# Power_Conversion.net
KiCad netlist of a schematic drawn in Altium Designer
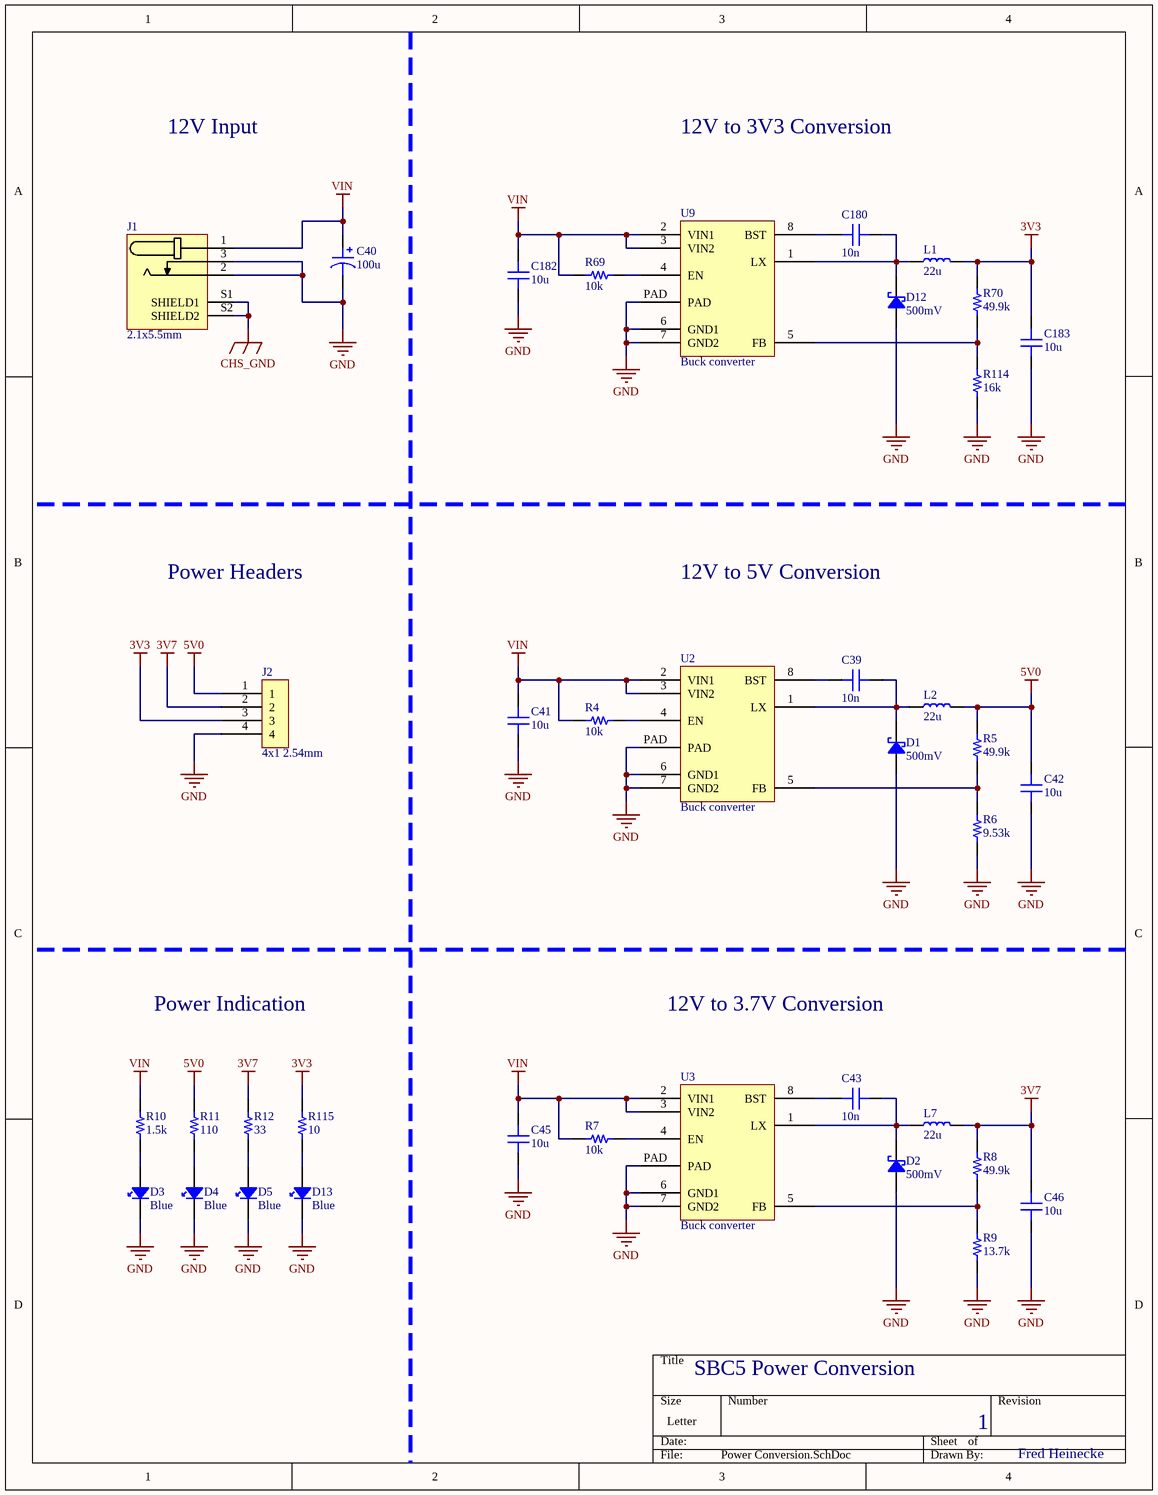
[diagram p0: Power Conversion.SchDoc]

(export (version "E")
  (design (tool "Eeschema 10.0.6"))
  (components
    (comp (ref "C39")
      (value "10n")
      (footprint "C0402")
      (fields
        (field (name "MANUFACTURER") "Samsung")
        (field (name "MANUFACTURER PART NUMBER") "CL05B103KO5NNNC")
        (field (name "TOLERANCE") "10%")
      )
      (libsource (lib "SBC5") (part "CL05B103KO5NNNC"))
    )
    (comp (ref "C40")
      (value "100u")
      (footprint "C8x11.5x3.5")
      (description "PANASONIC ELECTRONIC COMPONENTS - EEUFM1H101 - CAP, ALU ELEC, 100UF, 50V, RAD")
      (fields
        (field (name "MANUFACTURER") "Panasonic")
        (field (name "MANUFACTURER PART NUMBER") "EEU-FM1H101")
      )
      (libsource (lib "SBC5") (part "EEU-FM1H101"))
    )
    (comp (ref "C41")
      (value "10u")
      (footprint "C0805")
      (fields
        (field (name "MANUFACTURER") "Samsung")
        (field (name "MANUFACTURER PART NUMBER") "CL21A106KOQNNNE")
        (field (name "TOLERANCE") "10%")
      )
      (libsource (lib "SBC5") (part "CL21A106KOQNNNE"))
    )
    (comp (ref "C42")
      (value "10u")
      (footprint "C0805")
      (fields
        (field (name "MANUFACTURER") "Samsung")
        (field (name "MANUFACTURER PART NUMBER") "CL21A106KOQNNNE")
        (field (name "TOLERANCE") "10%")
      )
      (libsource (lib "SBC5") (part "CL21A106KOQNNNE"))
    )
    (comp (ref "C43")
      (value "10n")
      (footprint "C0402")
      (fields
        (field (name "MANUFACTURER") "Samsung")
        (field (name "MANUFACTURER PART NUMBER") "CL05B103KO5NNNC")
        (field (name "TOLERANCE") "10%")
      )
      (libsource (lib "SBC5") (part "CL05B103KO5NNNC"))
    )
    (comp (ref "C45")
      (value "10u")
      (footprint "C0805")
      (fields
        (field (name "MANUFACTURER") "Samsung")
        (field (name "MANUFACTURER PART NUMBER") "CL21A106KOQNNNE")
        (field (name "TOLERANCE") "10%")
      )
      (libsource (lib "SBC5") (part "CL21A106KOQNNNE"))
    )
    (comp (ref "C46")
      (value "10u")
      (footprint "C0805")
      (fields
        (field (name "MANUFACTURER") "Samsung")
        (field (name "MANUFACTURER PART NUMBER") "CL21A106KOQNNNE")
        (field (name "TOLERANCE") "10%")
      )
      (libsource (lib "SBC5") (part "CL21A106KOQNNNE"))
    )
    (comp (ref "C180")
      (value "10n")
      (footprint "C0402")
      (fields
        (field (name "MANUFACTURER") "Samsung")
        (field (name "MANUFACTURER PART NUMBER") "CL05B103KO5NNNC")
        (field (name "TOLERANCE") "10%")
      )
      (libsource (lib "SBC5") (part "CL05B103KO5NNNC"))
    )
    (comp (ref "C182")
      (value "10u")
      (footprint "C0805")
      (fields
        (field (name "MANUFACTURER") "Samsung")
        (field (name "MANUFACTURER PART NUMBER") "CL21A106KOQNNNE")
        (field (name "TOLERANCE") "10%")
      )
      (libsource (lib "SBC5") (part "CL21A106KOQNNNE"))
    )
    (comp (ref "C183")
      (value "10u")
      (footprint "C0805")
      (fields
        (field (name "MANUFACTURER") "Samsung")
        (field (name "MANUFACTURER PART NUMBER") "CL21A106KOQNNNE")
        (field (name "TOLERANCE") "10%")
      )
      (libsource (lib "SBC5") (part "CL21A106KOQNNNE"))
    )
    (comp (ref "D1")
      (value "500mV")
      (footprint "SOD-123")
      (description "Diode Schottky 30V 2A SOD123")
      (fields (field (name "MANUFACTURER") "SMC") (field (name "MANUFACTURER PART NUMBER") "MBR230LSTR"))
      (libsource (lib "SBC5") (part "MBR230LSTR"))
    )
    (comp (ref "D2")
      (value "500mV")
      (footprint "SOD-123")
      (description "Diode Schottky 30V 2A SOD123")
      (fields (field (name "MANUFACTURER") "SMC") (field (name "MANUFACTURER PART NUMBER") "MBR230LSTR"))
      (libsource (lib "SBC5") (part "MBR230LSTR"))
    )
    (comp (ref "D3")
      (value "Blue")
      (footprint "D0603")
      (description "WURTH ELEKTRONIK - 150060BS75000 - LED, Blau, Oberflächenmontage, 603, 30 mA, 3.2 V, 470 nm")
      (fields
        (field (name "MANUFACTURER") "Wurth Electronics")
        (field (name "MANUFACTURER PART NUMBER") "150060BS75000")
      )
      (libsource (lib "SBC5") (part "150060BS75000"))
    )
    (comp (ref "D4")
      (value "Blue")
      (footprint "D0603")
      (description "WURTH ELEKTRONIK - 150060BS75000 - LED, Blau, Oberflächenmontage, 603, 30 mA, 3.2 V, 470 nm")
      (fields
        (field (name "MANUFACTURER") "Wurth Electronics")
        (field (name "MANUFACTURER PART NUMBER") "150060BS75000")
      )
      (libsource (lib "SBC5") (part "150060BS75000"))
    )
    (comp (ref "D5")
      (value "Blue")
      (footprint "D0603")
      (description "WURTH ELEKTRONIK - 150060BS75000 - LED, Blau, Oberflächenmontage, 603, 30 mA, 3.2 V, 470 nm")
      (fields
        (field (name "MANUFACTURER") "Wurth Electronics")
        (field (name "MANUFACTURER PART NUMBER") "150060BS75000")
      )
      (libsource (lib "SBC5") (part "150060BS75000"))
    )
    (comp (ref "D12")
      (value "500mV")
      (footprint "SOD-123")
      (description "Diode Schottky 30V 2A SOD123")
      (fields (field (name "MANUFACTURER") "SMC") (field (name "MANUFACTURER PART NUMBER") "MBR230LSTR"))
      (libsource (lib "SBC5") (part "MBR230LSTR"))
    )
    (comp (ref "D13")
      (value "Blue")
      (footprint "D0603")
      (description "WURTH ELEKTRONIK - 150060BS75000 - LED, Blau, Oberflächenmontage, 603, 30 mA, 3.2 V, 470 nm")
      (fields
        (field (name "MANUFACTURER") "Wurth Electronics")
        (field (name "MANUFACTURER PART NUMBER") "150060BS75000")
      )
      (libsource (lib "SBC5") (part "150060BS75000"))
    )
    (comp (ref "J1")
      (value "2.1x5.5mm")
      (footprint "PJ-047AH")
      (description "CONN PWR JACK 2.1X5.5MM SOLDER")
      (fields (field (name "MANUFACTURER") "CUI") (field (name "MANUFACTURER PART NUMBER") "PJ-047AH"))
      (libsource (lib "SBC5") (part "PJ-047AH"))
    )
    (comp (ref "J2")
      (value "4x1 2.54mm")
      (footprint "PH1-04-UA")
      (description "Conn Unshrouded Header HDR 4 POS 2.54mm Solder ST Thru-Hole Bag")
      (fields
        (field (name "MANUFACTURER") "Adam Equipment")
        (field (name "MANUFACTURER PART NUMBER") "PH1-04-UA")
      )
      (libsource (lib "SBC5") (part "PH1-04-UA"))
    )
    (comp (ref "L1")
      (value "22u")
      (footprint "MPL-SE4030-220")
      (description "FIXED IND 22UH 1.5A 219 MOHM SMD")
      (fields
        (field (name "MANUFACTURER") "Monolithic Power Systems")
        (field (name "MANUFACTURER PART NUMBER") "MPL-SE4030-220")
      )
      (libsource (lib "SBC5") (part "MPL-SE4030-220"))
    )
    (comp (ref "L2")
      (value "22u")
      (footprint "MPL-SE4030-220")
      (description "FIXED IND 22UH 1.5A 219 MOHM SMD")
      (fields
        (field (name "MANUFACTURER") "Monolithic Power Systems")
        (field (name "MANUFACTURER PART NUMBER") "MPL-SE4030-220")
      )
      (libsource (lib "SBC5") (part "MPL-SE4030-220"))
    )
    (comp (ref "L7")
      (value "22u")
      (footprint "MPL-SE4030-220")
      (description "FIXED IND 22UH 1.5A 219 MOHM SMD")
      (fields
        (field (name "MANUFACTURER") "Monolithic Power Systems")
        (field (name "MANUFACTURER PART NUMBER") "MPL-SE4030-220")
      )
      (libsource (lib "SBC5") (part "MPL-SE4030-220"))
    )
    (comp (ref "R4")
      (value "10k")
      (footprint "R0201")
      (description "RES 10K OHM 1% 1/20W 0201")
      (fields
        (field (name "MANUFACTURER") "Stackpole Electronics")
        (field (name "MANUFACTURER PART NUMBER") "RMCF0201FT10K0")
      )
      (libsource (lib "SBC5") (part "RMCF0201FT10K0"))
    )
    (comp (ref "R5")
      (value "49.9k")
      (footprint "R0603")
      (description "RES SMD 49.9KOHM 0.1% 1/10W 0603")
      (fields
        (field (name "MANUFACTURER") "Panasonic")
        (field (name "MANUFACTURER PART NUMBER") "ERA-3AEB4992V")
      )
      (libsource (lib "SBC5") (part "ERA-3AEB4992V"))
    )
    (comp (ref "R6")
      (value "9.53k")
      (footprint "R0603")
      (description "RES SMD 9.53KOHM 0.1% 1/10W 0603")
      (fields
        (field (name "MANUFACTURER") "Panasonic")
        (field (name "MANUFACTURER PART NUMBER") "ERA-3AEB9531V")
      )
      (libsource (lib "SBC5") (part "ERA-3AEB9531V"))
    )
    (comp (ref "R7")
      (value "10k")
      (footprint "R0201")
      (description "RES 10K OHM 1% 1/20W 0201")
      (fields
        (field (name "MANUFACTURER") "Stackpole Electronics")
        (field (name "MANUFACTURER PART NUMBER") "RMCF0201FT10K0")
      )
      (libsource (lib "SBC5") (part "RMCF0201FT10K0"))
    )
    (comp (ref "R8")
      (value "49.9k")
      (footprint "R0603")
      (description "RES SMD 49.9KOHM 0.1% 1/10W 0603")
      (fields
        (field (name "MANUFACTURER") "Panasonic")
        (field (name "MANUFACTURER PART NUMBER") "ERA-3AEB4992V")
      )
      (libsource (lib "SBC5") (part "ERA-3AEB4992V"))
    )
    (comp (ref "R9")
      (value "13.7k")
      (footprint "R0603")
      (description "RES SMD 13.7K OHM 0.1% 1/5W 0603")
      (fields
        (field (name "MANUFACTURER") "Panasonic")
        (field (name "MANUFACTURER PART NUMBER") "ERJ-PB3B1372V")
      )
      (libsource (lib "SBC5") (part "ERJ-PB3B1372V"))
    )
    (comp (ref "R10")
      (value "1.5k")
      (footprint "R0402")
      (description "RES 1.5K OHM 1% 1/16W 0402")
      (fields
        (field (name "MANUFACTURER") "Stackpole Electronics")
        (field (name "MANUFACTURER PART NUMBER") "RMCF0402FT1K50")
      )
      (libsource (lib "SBC5") (part "RMCF0402FT1K50"))
    )
    (comp (ref "R11")
      (value "110")
      (footprint "R0402")
      (description "Res Thick Film 0402 110 Ohm 1% 0.063W(1/16W) ±100ppm/C Pad SMD Automotive T/R")
      (fields
        (field (name "MANUFACTURER") "Stackpole Electronics")
        (field (name "MANUFACTURER PART NUMBER") "RMCF0402FT110R")
      )
      (libsource (lib "SBC5") (part "RMCF0402FT110R"))
    )
    (comp (ref "R12")
      (value "33")
      (footprint "R0402")
      (description "RES 33 OHM 1% 1/16W 0402")
      (fields
        (field (name "MANUFACTURER") "Stackpole Electronics")
        (field (name "MANUFACTURER PART NUMBER") "RMCF0402FT33R0")
      )
      (libsource (lib "SBC5") (part "RMCF0402FT33R0"))
    )
    (comp (ref "R69")
      (value "10k")
      (footprint "R0201")
      (description "RES 10K OHM 1% 1/20W 0201")
      (fields
        (field (name "MANUFACTURER") "Stackpole Electronics")
        (field (name "MANUFACTURER PART NUMBER") "RMCF0201FT10K0")
      )
      (libsource (lib "SBC5") (part "RMCF0201FT10K0"))
    )
    (comp (ref "R70")
      (value "49.9k")
      (footprint "R0603")
      (description "RES SMD 49.9KOHM 0.1% 1/10W 0603")
      (fields
        (field (name "MANUFACTURER") "Panasonic")
        (field (name "MANUFACTURER PART NUMBER") "ERA-3AEB4992V")
      )
      (libsource (lib "SBC5") (part "ERA-3AEB4992V"))
    )
    (comp (ref "R114")
      (value "16k")
      (footprint "R0603")
      (description "RES SMD 16K OHM 1% 1/10W 0603")
      (fields
        (field (name "MANUFACTURER") "Stackpole Electronics")
        (field (name "MANUFACTURER PART NUMBER") "RMCF0603FT16K0")
      )
      (libsource (lib "SBC5") (part "RMCF0603FT16K0"))
    )
    (comp (ref "R115")
      (value "10")
      (footprint "R0402")
      (description "RES 10 OHM 1% 1/16W 0402")
      (fields
        (field (name "MANUFACTURER") "Stackpole Electronics")
        (field (name "MANUFACTURER PART NUMBER") "RMCF0402FT10R0")
      )
      (libsource (lib "SBC5") (part "RMCF0402FT10R0"))
    )
    (comp (ref "U2")
      (value "Buck converter")
      (footprint "AOZ1281DI")
      (description "Conv DC-DC 3V to 26V Step Down Single-Out 0.8V to 22.1V 1.8A 8-Pin DFN EP T/R")
      (fields
        (field (name "MANUFACTURER") "Alpha & Omega Semiconductor")
        (field (name "MANUFACTURER PART NUMBER") "AOZ1281DI")
      )
      (libsource (lib "SBC5") (part "AOZ1281DI"))
    )
    (comp (ref "U3")
      (value "Buck converter")
      (footprint "AOZ1281DI")
      (description "Conv DC-DC 3V to 26V Step Down Single-Out 0.8V to 22.1V 1.8A 8-Pin DFN EP T/R")
      (fields
        (field (name "MANUFACTURER") "Alpha & Omega Semiconductor")
        (field (name "MANUFACTURER PART NUMBER") "AOZ1281DI")
      )
      (libsource (lib "SBC5") (part "AOZ1281DI"))
    )
    (comp (ref "U9")
      (value "Buck converter")
      (footprint "AOZ1281DI")
      (description "Conv DC-DC 3V to 26V Step Down Single-Out 0.8V to 22.1V 1.8A 8-Pin DFN EP T/R")
      (fields
        (field (name "MANUFACTURER") "Alpha & Omega Semiconductor")
        (field (name "MANUFACTURER PART NUMBER") "AOZ1281DI")
      )
      (libsource (lib "SBC5") (part "AOZ1281DI"))
    )
  )
  (nets
    (net (code "1") (name "3V3") (class "Default")
      (node (ref "C183") (pin "2") (pinfunction "2_2") (pintype "passive"))
      (node (ref "J2") (pin "3") (pinfunction "3_3") (pintype "passive"))
      (node (ref "L1") (pin "2") (pinfunction "2_2") (pintype "passive"))
      (node (ref "R115") (pin "2") (pinfunction "2_2") (pintype "passive"))
      (node (ref "R70") (pin "2") (pinfunction "2_2") (pintype "passive"))
    )
    (net (code "2") (name "3V7") (class "Default")
      (node (ref "C46") (pin "2") (pinfunction "2_2") (pintype "passive"))
      (node (ref "J2") (pin "2") (pinfunction "2_2") (pintype "passive"))
      (node (ref "L7") (pin "2") (pinfunction "2_2") (pintype "passive"))
      (node (ref "R12") (pin "2") (pinfunction "2_2") (pintype "passive"))
      (node (ref "R8") (pin "2") (pinfunction "2_2") (pintype "passive"))
    )
    (net (code "3") (name "5V0") (class "Default")
      (node (ref "C42") (pin "2") (pinfunction "2_2") (pintype "passive"))
      (node (ref "J2") (pin "1") (pinfunction "1_1") (pintype "passive"))
      (node (ref "L2") (pin "2") (pinfunction "2_2") (pintype "passive"))
      (node (ref "R11") (pin "2") (pinfunction "2_2") (pintype "passive"))
      (node (ref "R5") (pin "2") (pinfunction "2_2") (pintype "passive"))
    )
    (net (code "4") (name "CHS_GND") (class "Default")
      (node (ref "J1") (pin "S1") (pinfunction "SHIELD1_S1") (pintype "passive"))
      (node (ref "J1") (pin "S2") (pinfunction "SHIELD2_S2") (pintype "passive"))
    )
    (net (code "5") (name "GND") (class "Default")
      (node (ref "C182") (pin "1") (pinfunction "1_1") (pintype "passive"))
      (node (ref "C183") (pin "1") (pinfunction "1_1") (pintype "passive"))
      (node (ref "C40") (pin "2") (pinfunction "2_2") (pintype "passive"))
      (node (ref "C41") (pin "1") (pinfunction "1_1") (pintype "passive"))
      (node (ref "C42") (pin "1") (pinfunction "1_1") (pintype "passive"))
      (node (ref "C45") (pin "1") (pinfunction "1_1") (pintype "passive"))
      (node (ref "C46") (pin "1") (pinfunction "1_1") (pintype "passive"))
      (node (ref "D1") (pin "2") (pinfunction "2_2") (pintype "passive"))
      (node (ref "D12") (pin "2") (pinfunction "2_2") (pintype "passive"))
      (node (ref "D13") (pin "K") (pinfunction "K_K") (pintype "passive"))
      (node (ref "D2") (pin "2") (pinfunction "2_2") (pintype "passive"))
      (node (ref "D3") (pin "K") (pinfunction "K_K") (pintype "passive"))
      (node (ref "D4") (pin "K") (pinfunction "K_K") (pintype "passive"))
      (node (ref "D5") (pin "K") (pinfunction "K_K") (pintype "passive"))
      (node (ref "J1") (pin "2") (pinfunction "2_2") (pintype "passive"))
      (node (ref "J1") (pin "3") (pinfunction "3_3") (pintype "passive"))
      (node (ref "J2") (pin "4") (pinfunction "4_4") (pintype "passive"))
      (node (ref "R114") (pin "1") (pinfunction "1_1") (pintype "passive"))
      (node (ref "R6") (pin "1") (pinfunction "1_1") (pintype "passive"))
      (node (ref "R9") (pin "1") (pinfunction "1_1") (pintype "passive"))
      (node (ref "U2") (pin "6") (pinfunction "GND1_6") (pintype "passive"))
      (node (ref "U2") (pin "7") (pinfunction "GND2_7") (pintype "passive"))
      (node (ref "U2") (pin "PAD") (pinfunction "PAD_PAD") (pintype "passive"))
      (node (ref "U3") (pin "6") (pinfunction "GND1_6") (pintype "passive"))
      (node (ref "U3") (pin "7") (pinfunction "GND2_7") (pintype "passive"))
      (node (ref "U3") (pin "PAD") (pinfunction "PAD_PAD") (pintype "passive"))
      (node (ref "U9") (pin "6") (pinfunction "GND1_6") (pintype "passive"))
      (node (ref "U9") (pin "7") (pinfunction "GND2_7") (pintype "passive"))
      (node (ref "U9") (pin "PAD") (pinfunction "PAD_PAD") (pintype "passive"))
    )
    (net (code "6") (name "Net-(D3-PadA)") (class "Default")
      (node (ref "D3") (pin "A") (pinfunction "A_A") (pintype "passive"))
      (node (ref "R10") (pin "1") (pinfunction "1_1") (pintype "passive"))
    )
    (net (code "7") (name "Net-(D4-PadA)") (class "Default")
      (node (ref "D4") (pin "A") (pinfunction "A_A") (pintype "passive"))
      (node (ref "R11") (pin "1") (pinfunction "1_1") (pintype "passive"))
    )
    (net (code "8") (name "Net-(D5-PadA)") (class "Default")
      (node (ref "D5") (pin "A") (pinfunction "A_A") (pintype "passive"))
      (node (ref "R12") (pin "1") (pinfunction "1_1") (pintype "passive"))
    )
    (net (code "9") (name "Net-(D13-PadA)") (class "Default")
      (node (ref "D13") (pin "A") (pinfunction "A_A") (pintype "passive"))
      (node (ref "R115") (pin "1") (pinfunction "1_1") (pintype "passive"))
    )
    (net (code "10") (name "Net-(U2-BST)") (class "Default")
      (node (ref "C39") (pin "1") (pinfunction "1_1") (pintype "passive"))
      (node (ref "U2") (pin "8") (pinfunction "BST_8") (pintype "passive"))
    )
    (net (code "11") (name "Net-(U2-EN)") (class "Default")
      (node (ref "R4") (pin "2") (pinfunction "2_2") (pintype "passive"))
      (node (ref "U2") (pin "4") (pinfunction "EN_4") (pintype "passive"))
    )
    (net (code "12") (name "Net-(U2-FB)") (class "Default")
      (node (ref "R5") (pin "1") (pinfunction "1_1") (pintype "passive"))
      (node (ref "R6") (pin "2") (pinfunction "2_2") (pintype "passive"))
      (node (ref "U2") (pin "5") (pinfunction "FB_5") (pintype "passive"))
    )
    (net (code "13") (name "Net-(U2-LX)") (class "Default")
      (node (ref "C39") (pin "2") (pinfunction "2_2") (pintype "passive"))
      (node (ref "D1") (pin "1") (pinfunction "1_1") (pintype "passive"))
      (node (ref "L2") (pin "1") (pinfunction "1_1") (pintype "passive"))
      (node (ref "U2") (pin "1") (pinfunction "LX_1") (pintype "passive"))
    )
    (net (code "14") (name "Net-(U3-BST)") (class "Default")
      (node (ref "C43") (pin "1") (pinfunction "1_1") (pintype "passive"))
      (node (ref "U3") (pin "8") (pinfunction "BST_8") (pintype "passive"))
    )
    (net (code "15") (name "Net-(U3-EN)") (class "Default")
      (node (ref "R7") (pin "2") (pinfunction "2_2") (pintype "passive"))
      (node (ref "U3") (pin "4") (pinfunction "EN_4") (pintype "passive"))
    )
    (net (code "16") (name "Net-(U3-FB)") (class "Default")
      (node (ref "R8") (pin "1") (pinfunction "1_1") (pintype "passive"))
      (node (ref "R9") (pin "2") (pinfunction "2_2") (pintype "passive"))
      (node (ref "U3") (pin "5") (pinfunction "FB_5") (pintype "passive"))
    )
    (net (code "17") (name "Net-(U3-LX)") (class "Default")
      (node (ref "C43") (pin "2") (pinfunction "2_2") (pintype "passive"))
      (node (ref "D2") (pin "1") (pinfunction "1_1") (pintype "passive"))
      (node (ref "L7") (pin "1") (pinfunction "1_1") (pintype "passive"))
      (node (ref "U3") (pin "1") (pinfunction "LX_1") (pintype "passive"))
    )
    (net (code "18") (name "Net-(U9-BST)") (class "Default")
      (node (ref "C180") (pin "1") (pinfunction "1_1") (pintype "passive"))
      (node (ref "U9") (pin "8") (pinfunction "BST_8") (pintype "passive"))
    )
    (net (code "19") (name "Net-(U9-EN)") (class "Default")
      (node (ref "R69") (pin "2") (pinfunction "2_2") (pintype "passive"))
      (node (ref "U9") (pin "4") (pinfunction "EN_4") (pintype "passive"))
    )
    (net (code "20") (name "Net-(U9-FB)") (class "Default")
      (node (ref "R114") (pin "2") (pinfunction "2_2") (pintype "passive"))
      (node (ref "R70") (pin "1") (pinfunction "1_1") (pintype "passive"))
      (node (ref "U9") (pin "5") (pinfunction "FB_5") (pintype "passive"))
    )
    (net (code "21") (name "Net-(U9-LX)") (class "Default")
      (node (ref "C180") (pin "2") (pinfunction "2_2") (pintype "passive"))
      (node (ref "D12") (pin "1") (pinfunction "1_1") (pintype "passive"))
      (node (ref "L1") (pin "1") (pinfunction "1_1") (pintype "passive"))
      (node (ref "U9") (pin "1") (pinfunction "LX_1") (pintype "passive"))
    )
    (net (code "22") (name "VIN") (class "Default")
      (node (ref "C182") (pin "2") (pinfunction "2_2") (pintype "passive"))
      (node (ref "C40") (pin "1") (pinfunction "1_1") (pintype "passive"))
      (node (ref "C41") (pin "2") (pinfunction "2_2") (pintype "passive"))
      (node (ref "C45") (pin "2") (pinfunction "2_2") (pintype "passive"))
      (node (ref "J1") (pin "1") (pinfunction "1_1") (pintype "passive"))
      (node (ref "R10") (pin "2") (pinfunction "2_2") (pintype "passive"))
      (node (ref "R4") (pin "1") (pinfunction "1_1") (pintype "passive"))
      (node (ref "R69") (pin "1") (pinfunction "1_1") (pintype "passive"))
      (node (ref "R7") (pin "1") (pinfunction "1_1") (pintype "passive"))
      (node (ref "U2") (pin "2") (pinfunction "VIN1_2") (pintype "passive"))
      (node (ref "U2") (pin "3") (pinfunction "VIN2_3") (pintype "passive"))
      (node (ref "U3") (pin "2") (pinfunction "VIN1_2") (pintype "passive"))
      (node (ref "U3") (pin "3") (pinfunction "VIN2_3") (pintype "passive"))
      (node (ref "U9") (pin "2") (pinfunction "VIN1_2") (pintype "passive"))
      (node (ref "U9") (pin "3") (pinfunction "VIN2_3") (pintype "passive"))
    )
  )
)
